# DRV8262_breakout_2024-04-23.net
KiCad netlist of a schematic drawn in EasyEDA Pro
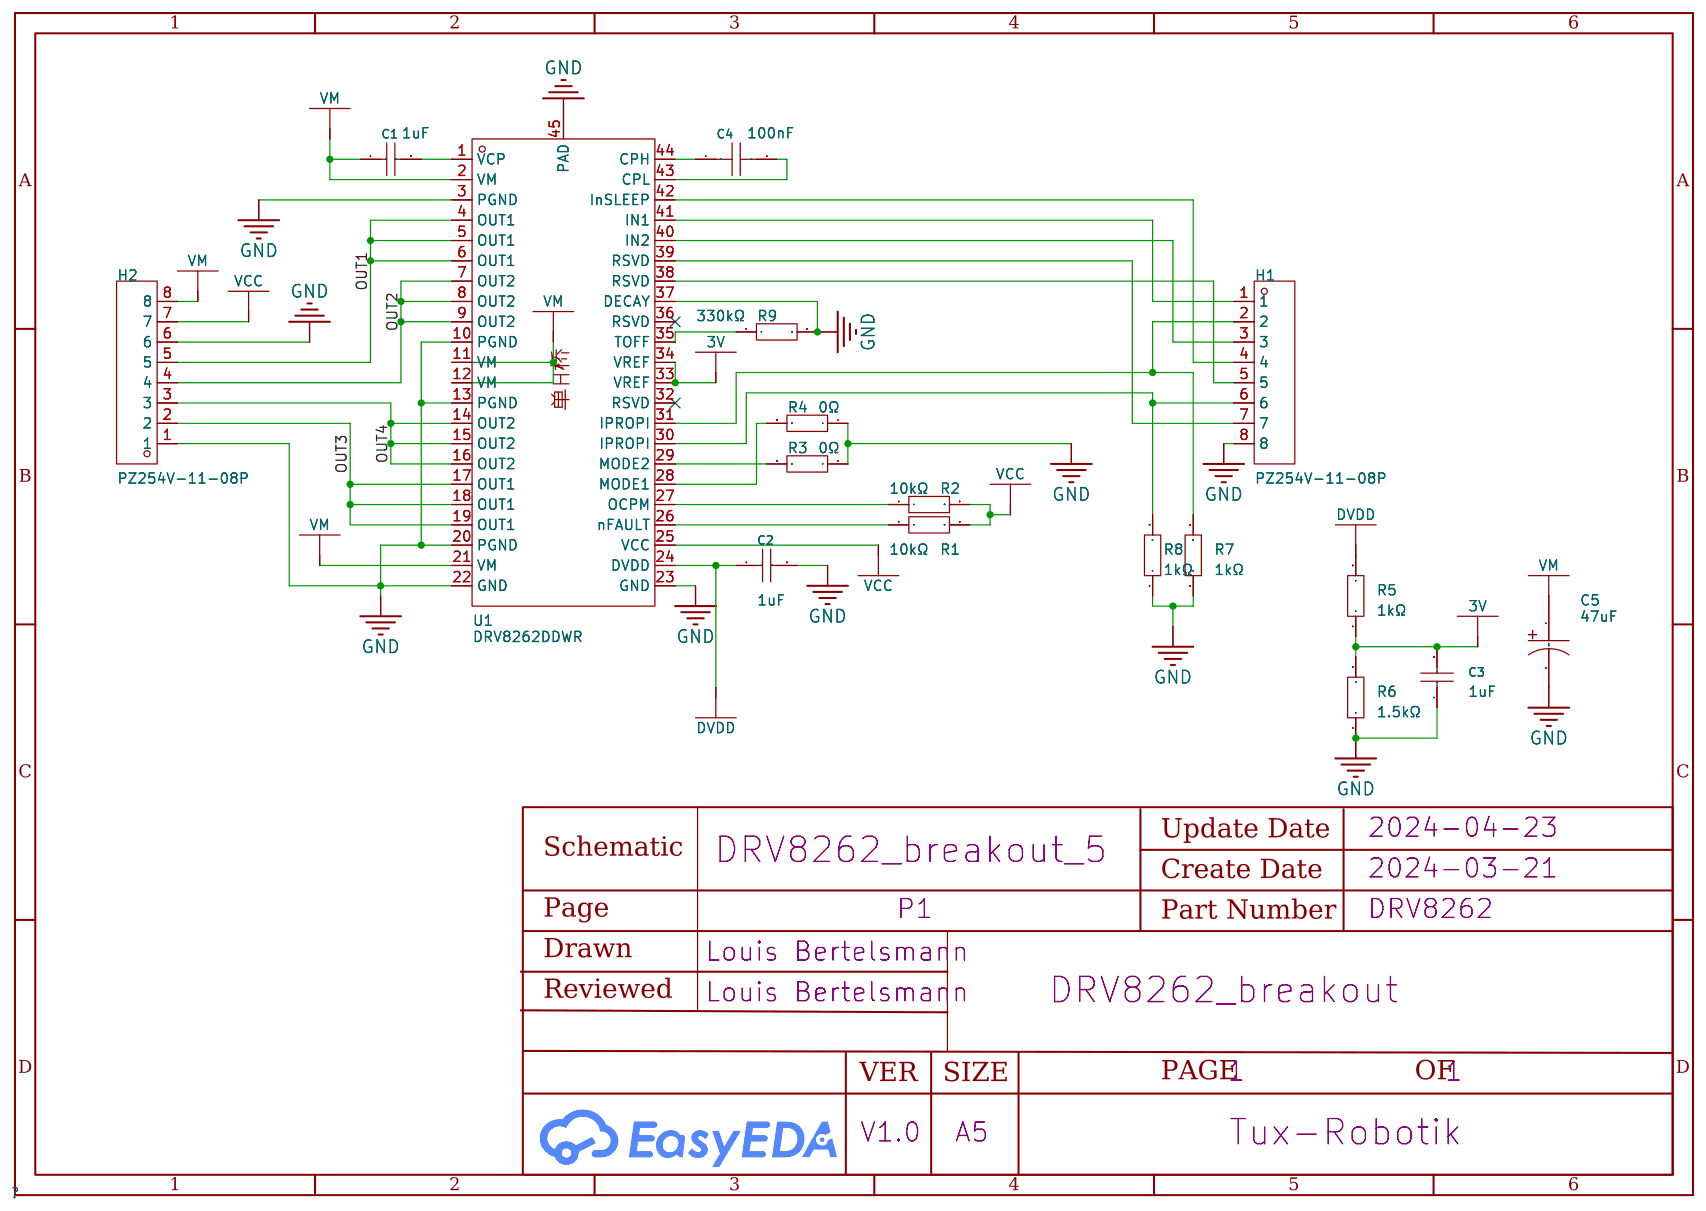
[diagram p0: schematic sheet]

(export (version "E")
  (design (tool "Eeschema 10.0.6"))
  (components
    (comp (ref "C1")
      (value "1uF")
      (footprint "easyedapro:C0603")
      (fields
        (field (name "Manufacturer Part") "CL10A105KB8NNNC")
        (field (name "Manufacturer") "SAMSUNG(三星)")
      )
      (libsource (lib "easyedapro") (part "CL10A105KB8NNNC"))
    )
    (comp (ref "C2")
      (value "1uF")
      (footprint "easyedapro:C0603")
      (fields
        (field (name "Manufacturer Part") "CL10A105KB8NNNC")
        (field (name "Manufacturer") "SAMSUNG(三星)")
      )
      (libsource (lib "easyedapro") (part "CL10A105KB8NNNC"))
    )
    (comp (ref "C3")
      (value "1uF")
      (footprint "easyedapro:C0603")
      (fields
        (field (name "Manufacturer Part") "CL10A105KB8NNNC")
        (field (name "Manufacturer") "SAMSUNG(三星)")
      )
      (libsource (lib "easyedapro") (part "CL10A105KB8NNNC"))
    )
    (comp (ref "C4")
      (value "100nF")
      (footprint "easyedapro:C0603")
      (fields
        (field (name "Manufacturer Part") "CL10B104KC8NNNC")
        (field (name "Manufacturer") "SAMSUNG(三星)")
      )
      (libsource (lib "easyedapro") (part "CL10B104KC8NNNC"))
    )
    (comp (ref "C5")
      (value "47uF")
      (footprint "easyedapro:CAP-SMD_BD6.3-L6.6-W6.6-LS7.2-FD")
      (fields
        (field (name "Manufacturer Part") "MVK25V47M6.3*5 6.3TP")
        (field (name "Manufacturer") "SAMYOUNG(韩国三莹)")
      )
      (libsource (lib "easyedapro") (part "MVK25VC47M6.3*5_6.3TP"))
    )
    (comp (ref "H1")
      (value "PZ254V-11-08P")
      (footprint "easyedapro:HDR-TH_8P-P2.54-V-M")
      (fields (field (name "Manufacturer") "XFCN(兴飞)"))
      (libsource (lib "easyedapro") (part "PZ254V-11-08P"))
    )
    (comp (ref "H2")
      (value "PZ254V-11-08P")
      (footprint "easyedapro:HDR-TH_8P-P2.54-V-M")
      (fields (field (name "Manufacturer") "XFCN(兴飞)"))
      (libsource (lib "easyedapro") (part "PZ254V-11-08P"))
    )
    (comp (ref "R1")
      (value "10kΩ")
      (footprint "easyedapro:R0603")
      (fields (field (name "Manufacturer Part") "AC0603FR-0710KL") (field (name "Manufacturer") "YAGEO(国巨)"))
      (libsource (lib "easyedapro") (part "AC0603FR-0710KL"))
    )
    (comp (ref "R2")
      (value "10kΩ")
      (footprint "easyedapro:R0603")
      (fields (field (name "Manufacturer Part") "AC0603FR-0710KL") (field (name "Manufacturer") "YAGEO(国巨)"))
      (libsource (lib "easyedapro") (part "AC0603FR-0710KL"))
    )
    (comp (ref "R3")
      (value "0Ω")
      (footprint "easyedapro:R0603")
      (fields (field (name "Manufacturer Part") "RC0603JR-070RL") (field (name "Manufacturer") "YAGEO(国巨)"))
      (libsource (lib "easyedapro") (part "RC0603JR-070RL"))
    )
    (comp (ref "R4")
      (value "0Ω")
      (footprint "easyedapro:R0603")
      (fields (field (name "Manufacturer Part") "RC0603JR-070RL") (field (name "Manufacturer") "YAGEO(国巨)"))
      (libsource (lib "easyedapro") (part "RC0603JR-070RL"))
    )
    (comp (ref "R5")
      (value "1kΩ")
      (footprint "easyedapro:R0603")
      (fields (field (name "Manufacturer Part") "RC0603FR-071KL") (field (name "Manufacturer") "YAGEO(国巨)"))
      (libsource (lib "easyedapro") (part "RC0603FR-071KL"))
    )
    (comp (ref "R6")
      (value "1.5kΩ")
      (footprint "easyedapro:R0603")
      (fields (field (name "Manufacturer Part") "RC0603FR-071K5L") (field (name "Manufacturer") "YAGEO(国巨)"))
      (libsource (lib "easyedapro") (part "RC0603FR-071K5L"))
    )
    (comp (ref "R7")
      (value "1kΩ")
      (footprint "easyedapro:R0603")
      (fields (field (name "Manufacturer Part") "RC0603FR-071KL") (field (name "Manufacturer") "YAGEO(国巨)"))
      (libsource (lib "easyedapro") (part "RC0603FR-071KL"))
    )
    (comp (ref "R8")
      (value "1kΩ")
      (footprint "easyedapro:R0603")
      (fields (field (name "Manufacturer Part") "RC0603FR-071KL") (field (name "Manufacturer") "YAGEO(国巨)"))
      (libsource (lib "easyedapro") (part "RC0603FR-071KL"))
    )
    (comp (ref "R9")
      (value "330kΩ")
      (footprint "easyedapro:R0603")
      (fields (field (name "Manufacturer Part") "RC0603FR-07330KL") (field (name "Manufacturer") "YAGEO(国巨)"))
      (libsource (lib "easyedapro") (part "RC0603FR-07330KL"))
    )
    (comp (ref "U1")
      (value "DRV8262DDWR")
      (footprint "easyedapro:HTSSOP-44_L14.0-W6.1-P0.64-LS8.1-BL-EP-2")
      (libsource (lib "easyedapro") (part "DRV8262DDWR"))
    )
  )
  (nets
    (net (code "1") (name "/OUT1") (class "Default")
      (node (ref "H2") (pin "5") (pinfunction "5_5") (pintype "unspecified"))
      (node (ref "U1") (pin "4") (pinfunction "OUT1_4") (pintype "unspecified"))
      (node (ref "U1") (pin "5") (pinfunction "OUT1_5") (pintype "unspecified"))
      (node (ref "U1") (pin "6") (pinfunction "OUT1_6") (pintype "unspecified"))
    )
    (net (code "2") (name "/OUT2") (class "Default")
      (node (ref "H2") (pin "4") (pinfunction "4_4") (pintype "unspecified"))
      (node (ref "U1") (pin "7") (pinfunction "OUT2_7") (pintype "unspecified"))
      (node (ref "U1") (pin "8") (pinfunction "OUT2_8") (pintype "unspecified"))
      (node (ref "U1") (pin "9") (pinfunction "OUT2_9") (pintype "unspecified"))
    )
    (net (code "3") (name "/OUT3") (class "Default")
      (node (ref "H2") (pin "2") (pinfunction "2_2") (pintype "unspecified"))
      (node (ref "U1") (pin "17") (pinfunction "OUT1_17") (pintype "unspecified"))
      (node (ref "U1") (pin "18") (pinfunction "OUT1_18") (pintype "unspecified"))
      (node (ref "U1") (pin "19") (pinfunction "OUT1_19") (pintype "unspecified"))
    )
    (net (code "4") (name "/OUT4") (class "Default")
      (node (ref "H2") (pin "3") (pinfunction "3_3") (pintype "unspecified"))
      (node (ref "U1") (pin "14") (pinfunction "OUT2_14") (pintype "unspecified"))
      (node (ref "U1") (pin "15") (pinfunction "OUT2_15") (pintype "unspecified"))
      (node (ref "U1") (pin "16") (pinfunction "OUT2_16") (pintype "unspecified"))
    )
    (net (code "5") (name "3V") (class "Default")
      (node (ref "C3") (pin "2") (pinfunction "2_2") (pintype "input"))
      (node (ref "R5") (pin "1") (pinfunction "1_1") (pintype "input"))
      (node (ref "R6") (pin "2") (pinfunction "2_2") (pintype "input"))
      (node (ref "U1") (pin "33") (pinfunction "VREF_33") (pintype "unspecified"))
      (node (ref "U1") (pin "34") (pinfunction "VREF_34") (pintype "unspecified"))
    )
    (net (code "6") (name "DVDD") (class "Default")
      (node (ref "C2") (pin "1") (pinfunction "1_1") (pintype "input"))
      (node (ref "R5") (pin "2") (pinfunction "2_2") (pintype "input"))
      (node (ref "U1") (pin "24") (pinfunction "DVDD_24") (pintype "unspecified"))
    )
    (net (code "7") (name "GND") (class "Default")
      (node (ref "C2") (pin "2") (pinfunction "2_2") (pintype "input"))
      (node (ref "C3") (pin "1") (pinfunction "1_1") (pintype "input"))
      (node (ref "C5") (pin "2") (pinfunction "2_2") (pintype "unspecified"))
      (node (ref "H1") (pin "8") (pinfunction "8_8") (pintype "unspecified"))
      (node (ref "H2") (pin "1") (pinfunction "1_1") (pintype "unspecified"))
      (node (ref "H2") (pin "6") (pinfunction "6_6") (pintype "unspecified"))
      (node (ref "R3") (pin "1") (pinfunction "1_1") (pintype "input"))
      (node (ref "R4") (pin "1") (pinfunction "1_1") (pintype "input"))
      (node (ref "R6") (pin "1") (pinfunction "1_1") (pintype "input"))
      (node (ref "R7") (pin "1") (pinfunction "1_1") (pintype "input"))
      (node (ref "R8") (pin "1") (pinfunction "1_1") (pintype "input"))
      (node (ref "R9") (pin "2") (pinfunction "2_2") (pintype "input"))
      (node (ref "U1") (pin "10") (pinfunction "PGND_10") (pintype "unspecified"))
      (node (ref "U1") (pin "13") (pinfunction "PGND_13") (pintype "unspecified"))
      (node (ref "U1") (pin "20") (pinfunction "PGND_20") (pintype "unspecified"))
      (node (ref "U1") (pin "22") (pinfunction "GND_22") (pintype "unspecified"))
      (node (ref "U1") (pin "23") (pinfunction "GND_23") (pintype "unspecified"))
      (node (ref "U1") (pin "3") (pinfunction "PGND_3") (pintype "unspecified"))
      (node (ref "U1") (pin "37") (pinfunction "DECAY_37") (pintype "unspecified"))
      (node (ref "U1") (pin "45") (pinfunction "PAD_45") (pintype "unspecified"))
    )
    (net (code "8") (name "Net-(H1-Pad2)") (class "Default")
      (node (ref "H1") (pin "2") (pinfunction "2_2") (pintype "unspecified"))
      (node (ref "R7") (pin "2") (pinfunction "2_2") (pintype "input"))
      (node (ref "U1") (pin "31") (pinfunction "IPROPI_31") (pintype "unspecified"))
    )
    (net (code "9") (name "Net-(H1-Pad5)") (class "Default")
      (node (ref "H1") (pin "5") (pinfunction "5_5") (pintype "unspecified"))
      (node (ref "U1") (pin "38") (pinfunction "RSVD_38") (pintype "unspecified"))
    )
    (net (code "10") (name "Net-(H1-Pad6)") (class "Default")
      (node (ref "H1") (pin "6") (pinfunction "6_6") (pintype "unspecified"))
      (node (ref "R8") (pin "2") (pinfunction "2_2") (pintype "input"))
      (node (ref "U1") (pin "30") (pinfunction "IPROPI_30") (pintype "unspecified"))
    )
    (net (code "11") (name "Net-(H1-Pad7)") (class "Default")
      (node (ref "H1") (pin "7") (pinfunction "7_7") (pintype "unspecified"))
      (node (ref "U1") (pin "39") (pinfunction "RSVD_39") (pintype "unspecified"))
    )
    (net (code "12") (name "Net-(U1-CPH)") (class "Default")
      (node (ref "C4") (pin "1") (pinfunction "1_1") (pintype "input"))
      (node (ref "U1") (pin "44") (pinfunction "CPH_44") (pintype "unspecified"))
    )
    (net (code "13") (name "Net-(U1-CPL)") (class "Default")
      (node (ref "C4") (pin "2") (pinfunction "2_2") (pintype "input"))
      (node (ref "U1") (pin "43") (pinfunction "CPL_43") (pintype "unspecified"))
    )
    (net (code "14") (name "Net-(U1-IN1)") (class "Default")
      (node (ref "H1") (pin "1") (pinfunction "1_1") (pintype "unspecified"))
      (node (ref "U1") (pin "41") (pinfunction "IN1_41") (pintype "unspecified"))
    )
    (net (code "15") (name "Net-(U1-IN2)") (class "Default")
      (node (ref "H1") (pin "3") (pinfunction "3_3") (pintype "unspecified"))
      (node (ref "U1") (pin "40") (pinfunction "IN2_40") (pintype "unspecified"))
    )
    (net (code "16") (name "Net-(U1-InSLEEP)") (class "Default")
      (node (ref "H1") (pin "4") (pinfunction "4_4") (pintype "unspecified"))
      (node (ref "U1") (pin "42") (pinfunction "InSLEEP_42") (pintype "unspecified"))
    )
    (net (code "17") (name "Net-(U1-MODE1)") (class "Default")
      (node (ref "R4") (pin "2") (pinfunction "2_2") (pintype "input"))
      (node (ref "U1") (pin "28") (pinfunction "MODE1_28") (pintype "unspecified"))
    )
    (net (code "18") (name "Net-(U1-MODE2)") (class "Default")
      (node (ref "R3") (pin "2") (pinfunction "2_2") (pintype "input"))
      (node (ref "U1") (pin "29") (pinfunction "MODE2_29") (pintype "unspecified"))
    )
    (net (code "19") (name "Net-(U1-OCPM)") (class "Default")
      (node (ref "R2") (pin "1") (pinfunction "1_1") (pintype "input"))
      (node (ref "U1") (pin "27") (pinfunction "OCPM_27") (pintype "unspecified"))
    )
    (net (code "20") (name "Net-(U1-TOFF)") (class "Default")
      (node (ref "R9") (pin "1") (pinfunction "1_1") (pintype "input"))
      (node (ref "U1") (pin "35") (pinfunction "TOFF_35") (pintype "unspecified"))
    )
    (net (code "21") (name "Net-(U1-VCP)") (class "Default")
      (node (ref "C1") (pin "2") (pinfunction "2_2") (pintype "input"))
      (node (ref "U1") (pin "1") (pinfunction "VCP_1") (pintype "unspecified"))
    )
    (net (code "22") (name "Net-(U1-nFAULT)") (class "Default")
      (node (ref "R1") (pin "1") (pinfunction "1_1") (pintype "input"))
      (node (ref "U1") (pin "26") (pinfunction "nFAULT_26") (pintype "unspecified"))
    )
    (net (code "23") (name "VCC") (class "Default")
      (node (ref "H2") (pin "7") (pinfunction "7_7") (pintype "unspecified"))
      (node (ref "R1") (pin "2") (pinfunction "2_2") (pintype "input"))
      (node (ref "R2") (pin "2") (pinfunction "2_2") (pintype "input"))
      (node (ref "U1") (pin "25") (pinfunction "VCC_25") (pintype "unspecified"))
    )
    (net (code "24") (name "VM") (class "Default")
      (node (ref "C1") (pin "1") (pinfunction "1_1") (pintype "input"))
      (node (ref "C5") (pin "1") (pinfunction "1_1") (pintype "unspecified"))
      (node (ref "H2") (pin "8") (pinfunction "8_8") (pintype "unspecified"))
      (node (ref "U1") (pin "11") (pinfunction "VM_11") (pintype "unspecified"))
      (node (ref "U1") (pin "12") (pinfunction "VM_12") (pintype "unspecified"))
      (node (ref "U1") (pin "2") (pinfunction "VM_2") (pintype "unspecified"))
      (node (ref "U1") (pin "21") (pinfunction "VM_21") (pintype "unspecified"))
    )
    (net (code "25") (name "unconnected-(U1-RSVD-Pad32)") (class "Default")
      (node (ref "U1") (pin "32") (pinfunction "RSVD_32") (pintype "unspecified+no_connect"))
    )
    (net (code "26") (name "unconnected-(U1-RSVD-Pad36)") (class "Default")
      (node (ref "U1") (pin "36") (pinfunction "RSVD_36") (pintype "unspecified+no_connect"))
    )
  )
)
